# Bus_Board.net
KiCad netlist of a schematic drawn in Altium Designer
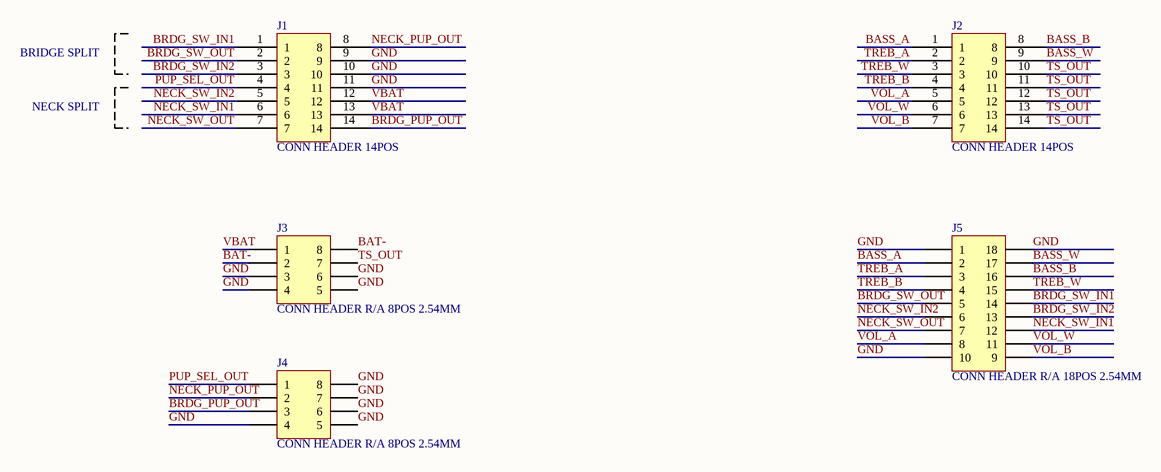
[diagram p0: Bus_Board.SchDoc]

(export (version "E")
  (design (tool "Eeschema 10.0.6"))
  (components
    (comp (ref "J1")
      (value "CONN HEADER 14POS")
      (footprint "DF12(3.0)-14DP")
      (description "14 Position Connector Header, Outer Shroud Contacts Surface Mount Gold")
      (fields (field (name "MANUFACTURER") "Hirose") (field (name "DIGIKEY PART NUMBER") "H11701CT-ND"))
      (libsource (lib "GuitarLibrary") (part "DF12(3.0)-14DP-0.5V(86)"))
    )
    (comp (ref "J2")
      (value "CONN HEADER 14POS")
      (footprint "DF12(3.0)-14DP")
      (description "14 Position Connector Header, Outer Shroud Contacts Surface Mount Gold")
      (fields (field (name "MANUFACTURER") "Hirose") (field (name "DIGIKEY PART NUMBER") "H11701CT-ND"))
      (libsource (lib "GuitarLibrary") (part "DF12(3.0)-14DP-0.5V(86)"))
    )
    (comp (ref "J3")
      (value "CONN HEADER R/A 8POS 2.54MM")
      (footprint "CONN HEADER R/A 8POS 2.54MM")
      (description "Connector Header Through Hole, Right Angle 8 position 0.100\" (2.54mm)")
      (fields (field (name "MANUFACTURER") "Samtec Inc.") (field (name "DIGIKEY PART NUMBER") "SAM12315-ND"))
      (libsource (lib "GuitarLibrary") (part "CONN HEADER R/A 8POS 2.54MM"))
    )
    (comp (ref "J4")
      (value "CONN HEADER R/A 8POS 2.54MM")
      (footprint "CONN HEADER R/A 8POS 2.54MM")
      (description "Connector Header Through Hole, Right Angle 8 position 0.100\" (2.54mm)")
      (fields (field (name "MANUFACTURER") "Samtec Inc.") (field (name "DIGIKEY PART NUMBER") "SAM12315-ND"))
      (libsource (lib "GuitarLibrary") (part "CONN HEADER R/A 8POS 2.54MM"))
    )
    (comp (ref "J5")
      (value "CONN HEADER R/A 18POS 2.54MM")
      (footprint "CONN HEADER R/A 18POS 2.54MM")
      (description "Connector Header Through Hole, Right Angle 18 position 0.100\" (2.54mm)")
      (fields
        (field (name "MANUFACTURER") "Samtec Inc.")
        (field (name "DIGIKEY PART NUMBER") "SAM1041-09-ND")
      )
      (libsource (lib "GuitarLibrary") (part "CONN HEADER R/A 18POS 2.54MM"))
    )
  )
  (nets
    (net (code "1") (name "/BASS_A") (class "Default")
      (node (ref "J2") (pin "1") (pinfunction "1_1") (pintype "passive"))
      (node (ref "J5") (pin "2") (pinfunction "2_2") (pintype "passive"))
    )
    (net (code "2") (name "/BASS_B") (class "Default")
      (node (ref "J2") (pin "8") (pinfunction "8_8") (pintype "passive"))
      (node (ref "J5") (pin "16") (pinfunction "16_16") (pintype "passive"))
    )
    (net (code "3") (name "/BASS_W") (class "Default")
      (node (ref "J2") (pin "9") (pinfunction "9_9") (pintype "passive"))
      (node (ref "J5") (pin "17") (pinfunction "17_17") (pintype "passive"))
    )
    (net (code "4") (name "/BAT-") (class "Default")
      (node (ref "J3") (pin "2") (pinfunction "2_2") (pintype "passive"))
      (node (ref "J3") (pin "8") (pinfunction "8_8") (pintype "passive"))
    )
    (net (code "5") (name "/BRDG_PUP_OUT") (class "Default")
      (node (ref "J1") (pin "14") (pinfunction "14_14") (pintype "passive"))
      (node (ref "J4") (pin "3") (pinfunction "3_3") (pintype "passive"))
    )
    (net (code "6") (name "/BRDG_SW_IN1") (class "Default")
      (node (ref "J1") (pin "1") (pinfunction "1_1") (pintype "passive"))
      (node (ref "J5") (pin "14") (pinfunction "14_14") (pintype "passive"))
    )
    (net (code "7") (name "/BRDG_SW_IN2") (class "Default")
      (node (ref "J1") (pin "3") (pinfunction "3_3") (pintype "passive"))
      (node (ref "J5") (pin "13") (pinfunction "13_13") (pintype "passive"))
    )
    (net (code "8") (name "/BRDG_SW_OUT") (class "Default")
      (node (ref "J1") (pin "2") (pinfunction "2_2") (pintype "passive"))
      (node (ref "J5") (pin "5") (pinfunction "5_5") (pintype "passive"))
    )
    (net (code "9") (name "/GND") (class "Default")
      (node (ref "J1") (pin "10") (pinfunction "10_10") (pintype "passive"))
      (node (ref "J1") (pin "11") (pinfunction "11_11") (pintype "passive"))
      (node (ref "J1") (pin "9") (pinfunction "9_9") (pintype "passive"))
      (node (ref "J3") (pin "3") (pinfunction "3_3") (pintype "passive"))
      (node (ref "J3") (pin "4") (pinfunction "4_4") (pintype "passive"))
      (node (ref "J3") (pin "5") (pinfunction "5_5") (pintype "passive"))
      (node (ref "J3") (pin "6") (pinfunction "6_6") (pintype "passive"))
      (node (ref "J4") (pin "4") (pinfunction "4_4") (pintype "passive"))
      (node (ref "J4") (pin "5") (pinfunction "5_5") (pintype "passive"))
      (node (ref "J4") (pin "6") (pinfunction "6_6") (pintype "passive"))
      (node (ref "J4") (pin "7") (pinfunction "7_7") (pintype "passive"))
      (node (ref "J4") (pin "8") (pinfunction "8_8") (pintype "passive"))
      (node (ref "J5") (pin "1") (pinfunction "1_1") (pintype "passive"))
      (node (ref "J5") (pin "10") (pinfunction "10_10") (pintype "passive"))
      (node (ref "J5") (pin "18") (pinfunction "18_18") (pintype "passive"))
    )
    (net (code "10") (name "/NECK_PUP_OUT") (class "Default")
      (node (ref "J1") (pin "8") (pinfunction "8_8") (pintype "passive"))
      (node (ref "J4") (pin "2") (pinfunction "2_2") (pintype "passive"))
    )
    (net (code "11") (name "/NECK_SW_IN1") (class "Default")
      (node (ref "J1") (pin "6") (pinfunction "6_6") (pintype "passive"))
      (node (ref "J5") (pin "12") (pinfunction "12_12") (pintype "passive"))
    )
    (net (code "12") (name "/NECK_SW_IN2") (class "Default")
      (node (ref "J1") (pin "5") (pinfunction "5_5") (pintype "passive"))
      (node (ref "J5") (pin "6") (pinfunction "6_6") (pintype "passive"))
    )
    (net (code "13") (name "/NECK_SW_OUT") (class "Default")
      (node (ref "J1") (pin "7") (pinfunction "7_7") (pintype "passive"))
      (node (ref "J5") (pin "7") (pinfunction "7_7") (pintype "passive"))
    )
    (net (code "14") (name "/PUP_SEL_OUT") (class "Default")
      (node (ref "J1") (pin "4") (pinfunction "4_4") (pintype "passive"))
      (node (ref "J4") (pin "1") (pinfunction "1_1") (pintype "passive"))
    )
    (net (code "15") (name "/TREB_A") (class "Default")
      (node (ref "J2") (pin "2") (pinfunction "2_2") (pintype "passive"))
      (node (ref "J5") (pin "3") (pinfunction "3_3") (pintype "passive"))
    )
    (net (code "16") (name "/TREB_B") (class "Default")
      (node (ref "J2") (pin "4") (pinfunction "4_4") (pintype "passive"))
      (node (ref "J5") (pin "4") (pinfunction "4_4") (pintype "passive"))
    )
    (net (code "17") (name "/TREB_W") (class "Default")
      (node (ref "J2") (pin "3") (pinfunction "3_3") (pintype "passive"))
      (node (ref "J5") (pin "15") (pinfunction "15_15") (pintype "passive"))
    )
    (net (code "18") (name "/TS_OUT") (class "Default")
      (node (ref "J2") (pin "10") (pinfunction "10_10") (pintype "passive"))
      (node (ref "J2") (pin "11") (pinfunction "11_11") (pintype "passive"))
      (node (ref "J2") (pin "12") (pinfunction "12_12") (pintype "passive"))
      (node (ref "J2") (pin "13") (pinfunction "13_13") (pintype "passive"))
      (node (ref "J2") (pin "14") (pinfunction "14_14") (pintype "passive"))
      (node (ref "J3") (pin "7") (pinfunction "7_7") (pintype "passive"))
    )
    (net (code "19") (name "/VBAT") (class "Default")
      (node (ref "J1") (pin "12") (pinfunction "12_12") (pintype "passive"))
      (node (ref "J1") (pin "13") (pinfunction "13_13") (pintype "passive"))
      (node (ref "J3") (pin "1") (pinfunction "1_1") (pintype "passive"))
    )
    (net (code "20") (name "/VOL_A") (class "Default")
      (node (ref "J2") (pin "5") (pinfunction "5_5") (pintype "passive"))
      (node (ref "J5") (pin "8") (pinfunction "8_8") (pintype "passive"))
    )
    (net (code "21") (name "/VOL_B") (class "Default")
      (node (ref "J2") (pin "7") (pinfunction "7_7") (pintype "passive"))
      (node (ref "J5") (pin "9") (pinfunction "9_9") (pintype "passive"))
    )
    (net (code "22") (name "/VOL_W") (class "Default")
      (node (ref "J2") (pin "6") (pinfunction "6_6") (pintype "passive"))
      (node (ref "J5") (pin "11") (pinfunction "11_11") (pintype "passive"))
    )
  )
)
